# FET_PWM_output.net
KiCad netlist of a schematic drawn in Altium Designer
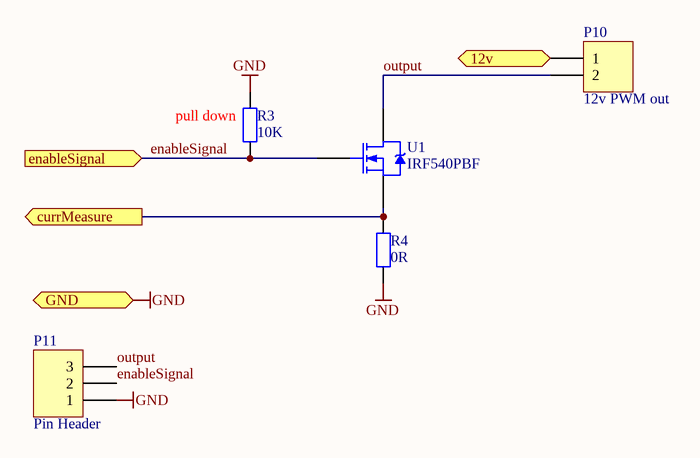
[diagram p0: FET PWM output.SchDoc]

(export (version "E")
  (design (tool "Eeschema 10.0.6"))
  (components
    (comp (ref "P10")
      (value "12v PWM out")
      (footprint "TB2_5.08")
      (description "Con1x2")
      (fields
        (field (name "PART NUMBER") "TB2")
        (field (name "VOLTAGE") "300")
        (field (name "AUTHOR") "Bram van Rensen")
      )
      (libsource (lib "OurDb") (part "Con1x2"))
    )
    (comp (ref "P11")
      (value "Pin Header")
      (footprint "PH1x3_2.54")
      (description "Con1x3")
      (fields (field (name "PART NUMBER") "PH1x3") (field (name "AUTHOR") "Willy Pietersz"))
      (libsource (lib "OurDb") (part "Con1x3"))
    )
    (comp (ref "R3")
      (value "10K")
      (footprint "R0805")
      (description "Resistor")
      (fields
        (field (name "POWER") "0.25W")
        (field (name "TOLERANCE") "0.05")
        (field (name "PUBLISHER") "Altium Limited")
        (field (name "AUTHOR") "Willy Pietersz")
      )
      (libsource (lib "OurDb") (part "RESISTOR"))
    )
    (comp (ref "R4")
      (value "0R")
      (footprint "R0805")
      (description "Resistor")
      (fields (field (name "Comment") "RESISTOR") (field (name "PUBLISHER") "Altium Limited"))
      (libsource (lib "OurDb") (part "RESISTOR"))
    )
    (comp (ref "U1")
      (value "IRF540PBF")
      (footprint "TO-220AB")
      (description "Transistor")
      (fields (field (name "VOLTAGE") "100") (field (name "AUTHOR") "Willy Pietersz"))
      (libsource (lib "OurDb") (part "NMOS"))
    )
  )
  (nets
    (net (code "1") (name "/12v") (class "Default")
      (node (ref "P10") (pin "1") (pinfunction "1_1") (pintype "passive"))
    )
    (net (code "2") (name "/currMeasure") (class "Default")
      (node (ref "R4") (pin "1") (pinfunction "1_1") (pintype "passive"))
      (node (ref "U1") (pin "3") (pinfunction "S_3") (pintype "passive"))
    )
    (net (code "3") (name "/enableSignal") (class "Default")
      (node (ref "P11") (pin "2") (pinfunction "2_2") (pintype "passive"))
      (node (ref "R3") (pin "2") (pinfunction "2_2") (pintype "passive"))
      (node (ref "U1") (pin "1") (pinfunction "G_1") (pintype "passive"))
    )
    (net (code "4") (name "/output") (class "Default")
      (node (ref "P10") (pin "2") (pinfunction "2_2") (pintype "passive"))
      (node (ref "P11") (pin "3") (pinfunction "3_3") (pintype "passive"))
      (node (ref "U1") (pin "2") (pinfunction "D_2") (pintype "passive"))
    )
    (net (code "5") (name "GND") (class "Default")
      (node (ref "P11") (pin "1") (pinfunction "1_1") (pintype "passive"))
      (node (ref "R3") (pin "1") (pinfunction "1_1") (pintype "passive"))
      (node (ref "R4") (pin "2") (pinfunction "2_2") (pintype "passive"))
    )
  )
)
